# LDO_3V3.net
KiCad netlist of a schematic drawn in Altium Designer
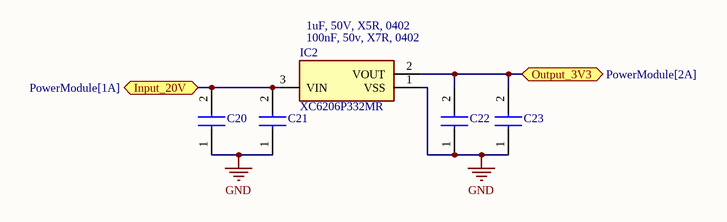
[diagram p0: LDO_3V3.SchDoc]

(export (version "E")
  (design (tool "Eeschema 10.0.6"))
  (components
    (comp (ref "C20")
      (value "1uF, 50V, X5R, 0402")
      (footprint "SamacSys:GRM15x")
      (description "Capacitor")
      (fields
        (field (name "MANUFACTURER_PART_NUMBER") "GRM155R61H105KE05J")
        (field (name "MOUSER PART NUMBER") "81-GRM155R61H105KE5J")
      )
      (libsource (lib "*") (part "GRM155R61H105KE05J"))
    )
    (comp (ref "C21")
      (value "100nF, 50v, X7R, 0402")
      (footprint "SamacSys:CAPC2012X88N")
      (description "Capacitor")
      (fields
        (field (name "MANUFACTURER_PART_NUMBER") "C0805C104M5RAC")
        (field (name "MOUSER PART NUMBER") "80-C0805C104M5RAC")
      )
      (libsource (lib "*") (part "C0805C104M5RAC"))
    )
    (comp (ref "C22")
      (value "100nF, 50v, X7R, 0402")
      (footprint "SamacSys:CAPC2012X88N")
      (description "Capacitor")
      (fields
        (field (name "MANUFACTURER_PART_NUMBER") "C0805C104M5RAC")
        (field (name "MOUSER PART NUMBER") "80-C0805C104M5RAC")
      )
      (libsource (lib "*") (part "C0805C104M5RAC"))
    )
    (comp (ref "C23")
      (value "1uF, 50V, X5R, 0402")
      (footprint "SamacSys:GRM15x")
      (description "Capacitor")
      (fields
        (field (name "MANUFACTURER_PART_NUMBER") "GRM155R61H105KE05J")
        (field (name "MOUSER PART NUMBER") "81-GRM155R61H105KE5J")
      )
      (libsource (lib "*") (part "GRM155R61H105KE05J"))
    )
    (comp (ref "IC2")
      (value "XC6206P332MR")
      (footprint "SamacSys:SOT95P280X130-3N")
      (description "Integrated Circuit")
      (libsource (lib "*") (part "XC6206P332MR"))
    )
  )
  (nets
    (net (code "1") (name "/Input_20V") (class "Default")
      (node (ref "C20") (pin "2") (pinfunction "2_2") (pintype "passive"))
      (node (ref "C21") (pin "2") (pinfunction "2_2") (pintype "passive"))
      (node (ref "IC2") (pin "3") (pinfunction "VIN_3") (pintype "passive"))
    )
    (net (code "2") (name "/Output_3V3") (class "Default")
      (node (ref "C22") (pin "2") (pinfunction "2_2") (pintype "passive"))
      (node (ref "C23") (pin "2") (pinfunction "2_2") (pintype "passive"))
      (node (ref "IC2") (pin "2") (pinfunction "VOUT_2") (pintype "passive"))
    )
    (net (code "3") (name "GND") (class "Default")
      (node (ref "C20") (pin "1") (pinfunction "1_1") (pintype "passive"))
      (node (ref "C21") (pin "1") (pinfunction "1_1") (pintype "passive"))
      (node (ref "C22") (pin "1") (pinfunction "1_1") (pintype "passive"))
      (node (ref "C23") (pin "1") (pinfunction "1_1") (pintype "passive"))
      (node (ref "IC2") (pin "1") (pinfunction "VSS_1") (pintype "passive"))
    )
  )
)
